# YOTSUBA__Y_Z_ver_1_3.net
KiCad netlist of a schematic drawn in EAGLE
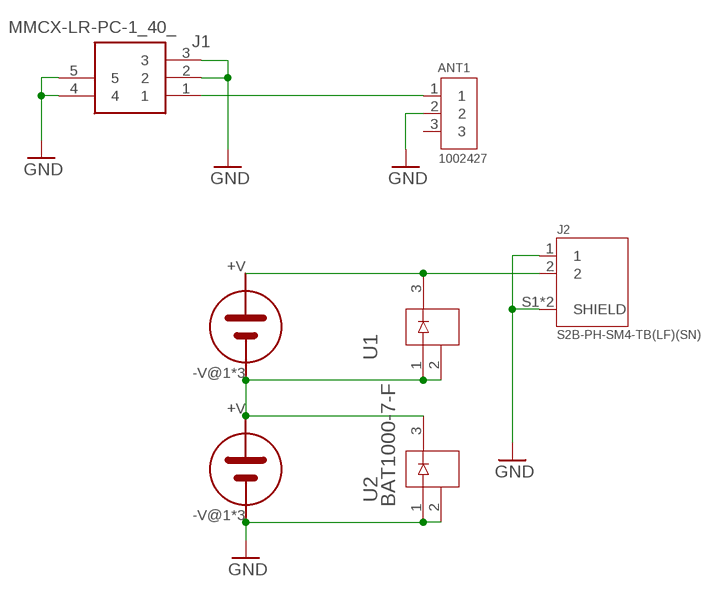
[diagram p0: schematic, sheet 1]

(export (version "E")
  (design (tool "Eeschema 10.0.6"))
  (components
    (comp (ref "ANT1")
      (value "1002427")
      (footprint "eagle-import:ANTENNA_1002427")
      (fields (field (name "DIGI-KEY_PART_NUMBER") "478-1002427TR-ND") (field (name "MF") "Ethertronics/AVX"))
      (libsource (lib "eagle-import") (part "1002427"))
    )
    (comp (ref "J1")
      (value "MMCX-LR-PC-1_40_")
      (footprint "eagle-import:MMCXLRPC140")
      (fields
        (field (name "MANUFACTURER_PART_NUMBER") "MMCX-LR-PC-1(40)")
        (field (name "MOUSER_PART_NUMBER") "798-MMCX-LR-PC-1(40)")
      )
      (libsource (lib "eagle-import") (part "MMCX-LR-PC-1_40_"))
    )
    (comp (ref "J2")
      (value "S2B-PH-SM4-TB(LF)(SN)")
      (footprint "eagle-import:JST_S2B-PH-SM4-TB(LF)(SN)")
      (fields (field (name "DIGI-KEY_PART_NUMBER") "455-1749-2-ND") (field (name "MF") "JST Sales"))
      (libsource (lib "eagle-import") (part "S2B-PH-SM4-TB(LF)(SN)"))
    )
    (comp (ref "U$2")
      (value "3G30A")
      (footprint "eagle-import:SOLAR_3G30A")
      (libsource (lib "eagle-import") (part "3G30A"))
    )
    (comp (ref "U$3")
      (value "3G30A")
      (footprint "eagle-import:SOLAR_3G30A")
      (libsource (lib "eagle-import") (part "3G30A"))
    )
    (comp (ref "U1")
      (value "BAT1000-7-F")
      (footprint "eagle-import:SOT23_BAT_DIO")
      (fields (field (name "COPYRIGHT") "Copyright (C) 2023 Ultra Librarian. All rights reserved."))
      (libsource (lib "eagle-import") (part "BAT1000-7-F"))
    )
    (comp (ref "U2")
      (value "BAT1000-7-F")
      (footprint "eagle-import:SOT23_BAT_DIO")
      (fields (field (name "COPYRIGHT") "Copyright (C) 2023 Ultra Librarian. All rights reserved."))
      (libsource (lib "eagle-import") (part "BAT1000-7-F"))
    )
  )
  (nets
    (net (code "1") (name "GND") (class "Default")
      (node (ref "ANT1") (pin "2") (pinfunction "2_2") (pintype "passive"))
      (node (ref "J1") (pin "2") (pinfunction "2_2") (pintype "bidirectional"))
      (node (ref "J1") (pin "3") (pinfunction "3_3") (pintype "bidirectional"))
      (node (ref "J1") (pin "4") (pinfunction "4_4") (pintype "bidirectional"))
      (node (ref "J1") (pin "5") (pinfunction "5_5") (pintype "bidirectional"))
      (node (ref "J2") (pin "1") (pinfunction "1_1") (pintype "passive"))
      (node (ref "J2") (pin "S1") (pinfunction "SHIELD_S1") (pintype "passive"))
      (node (ref "J2") (pin "S2") (pinfunction "SHIELD_S2") (pintype "passive"))
      (node (ref "U$3") (pin "-V@1") (pinfunction "-V_-V@1") (pintype "bidirectional"))
      (node (ref "U$3") (pin "-V@2") (pinfunction "-V_-V@2") (pintype "bidirectional"))
      (node (ref "U$3") (pin "-V@3") (pinfunction "-V_-V@3") (pintype "bidirectional"))
      (node (ref "U2") (pin "1") (pinfunction "1_1") (pintype "passive"))
      (node (ref "U2") (pin "2") (pinfunction "2_2") (pintype "passive"))
    )
    (net (code "2") (name "Net-(ANT1-Pad1)") (class "Default")
      (node (ref "ANT1") (pin "1") (pinfunction "1_1") (pintype "passive"))
      (node (ref "J1") (pin "1") (pinfunction "1_1") (pintype "bidirectional"))
    )
    (net (code "3") (name "Net-(J2-Pad2)") (class "Default")
      (node (ref "J2") (pin "2") (pinfunction "2_2") (pintype "passive"))
      (node (ref "U$2") (pin "+V") (pinfunction "+V_+V") (pintype "bidirectional"))
      (node (ref "U1") (pin "3") (pinfunction "3_3") (pintype "passive"))
    )
    (net (code "4") (name "Net-(U$2--V-Pad-V@1)") (class "Default")
      (node (ref "U$2") (pin "-V@1") (pinfunction "-V_-V@1") (pintype "bidirectional"))
      (node (ref "U$2") (pin "-V@2") (pinfunction "-V_-V@2") (pintype "bidirectional"))
      (node (ref "U$2") (pin "-V@3") (pinfunction "-V_-V@3") (pintype "bidirectional"))
      (node (ref "U$3") (pin "+V") (pinfunction "+V_+V") (pintype "bidirectional"))
      (node (ref "U1") (pin "1") (pinfunction "1_1") (pintype "passive"))
      (node (ref "U1") (pin "2") (pinfunction "2_2") (pintype "passive"))
      (node (ref "U2") (pin "3") (pinfunction "3_3") (pintype "passive"))
    )
    (net (code "5") (name "unconnected-(ANT1-Pad3)") (class "Default")
      (node (ref "ANT1") (pin "3") (pinfunction "3_3") (pintype "passive"))
    )
  )
)
